# Printer.net
KiCad netlist of a schematic drawn in Altium Designer
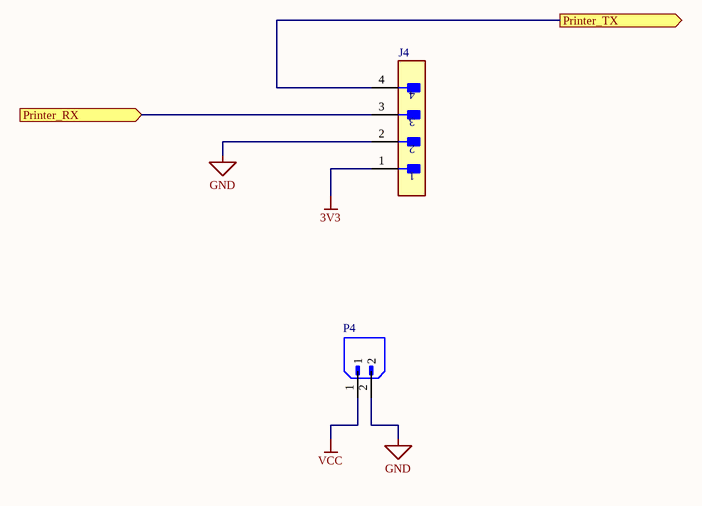
[diagram p0: Printer.SchDoc]

(export (version "E")
  (design (tool "Eeschema 10.0.6"))
  (components
    (comp (ref "J4")
      (value "B04B-XASK-1(LF)(SN)")
      (footprint "FP-B04B-XASK-1_LF_SN-MFG")
      (description "CONN HEADER VERT 4POS 2.5MM")
      (fields
        (field (name "OCTOPART") "https://octopart.com/b04b-xask-1%28lf%29%28sn%29-jst-3990149")
        (field (name "MANUFACTURER") "JST")
      )
      (libsource (lib "Altium Content Vault") (part "299a8cea1bdcbc3624fe62c390fa72c"))
    )
    (comp (ref "P4")
      (value "Battery Connector")
      (footprint "JST_B2B-XH-A(LF)(SN)")
      (libsource (lib "SchemLib") (part "TX_RX Header"))
    )
  )
  (nets
    (net (code "1") (name "/Printer_RX") (class "Default")
      (node (ref "J4") (pin "3") (pinfunction "3_3") (pintype "passive"))
    )
    (net (code "2") (name "/Printer_TX") (class "Default")
      (node (ref "J4") (pin "4") (pinfunction "4_4") (pintype "passive"))
    )
    (net (code "3") (name "3V3") (class "Default")
      (node (ref "J4") (pin "1") (pinfunction "1_1") (pintype "passive"))
    )
    (net (code "4") (name "GND") (class "Default")
      (node (ref "J4") (pin "2") (pinfunction "2_2") (pintype "passive"))
      (node (ref "P4") (pin "2") (pinfunction "2_2") (pintype "passive"))
    )
    (net (code "5") (name "VCC") (class "Default")
      (node (ref "P4") (pin "1") (pinfunction "1_1") (pintype "passive"))
    )
  )
)
